# garden.net
KiCad netlist of a schematic drawn in EAGLE
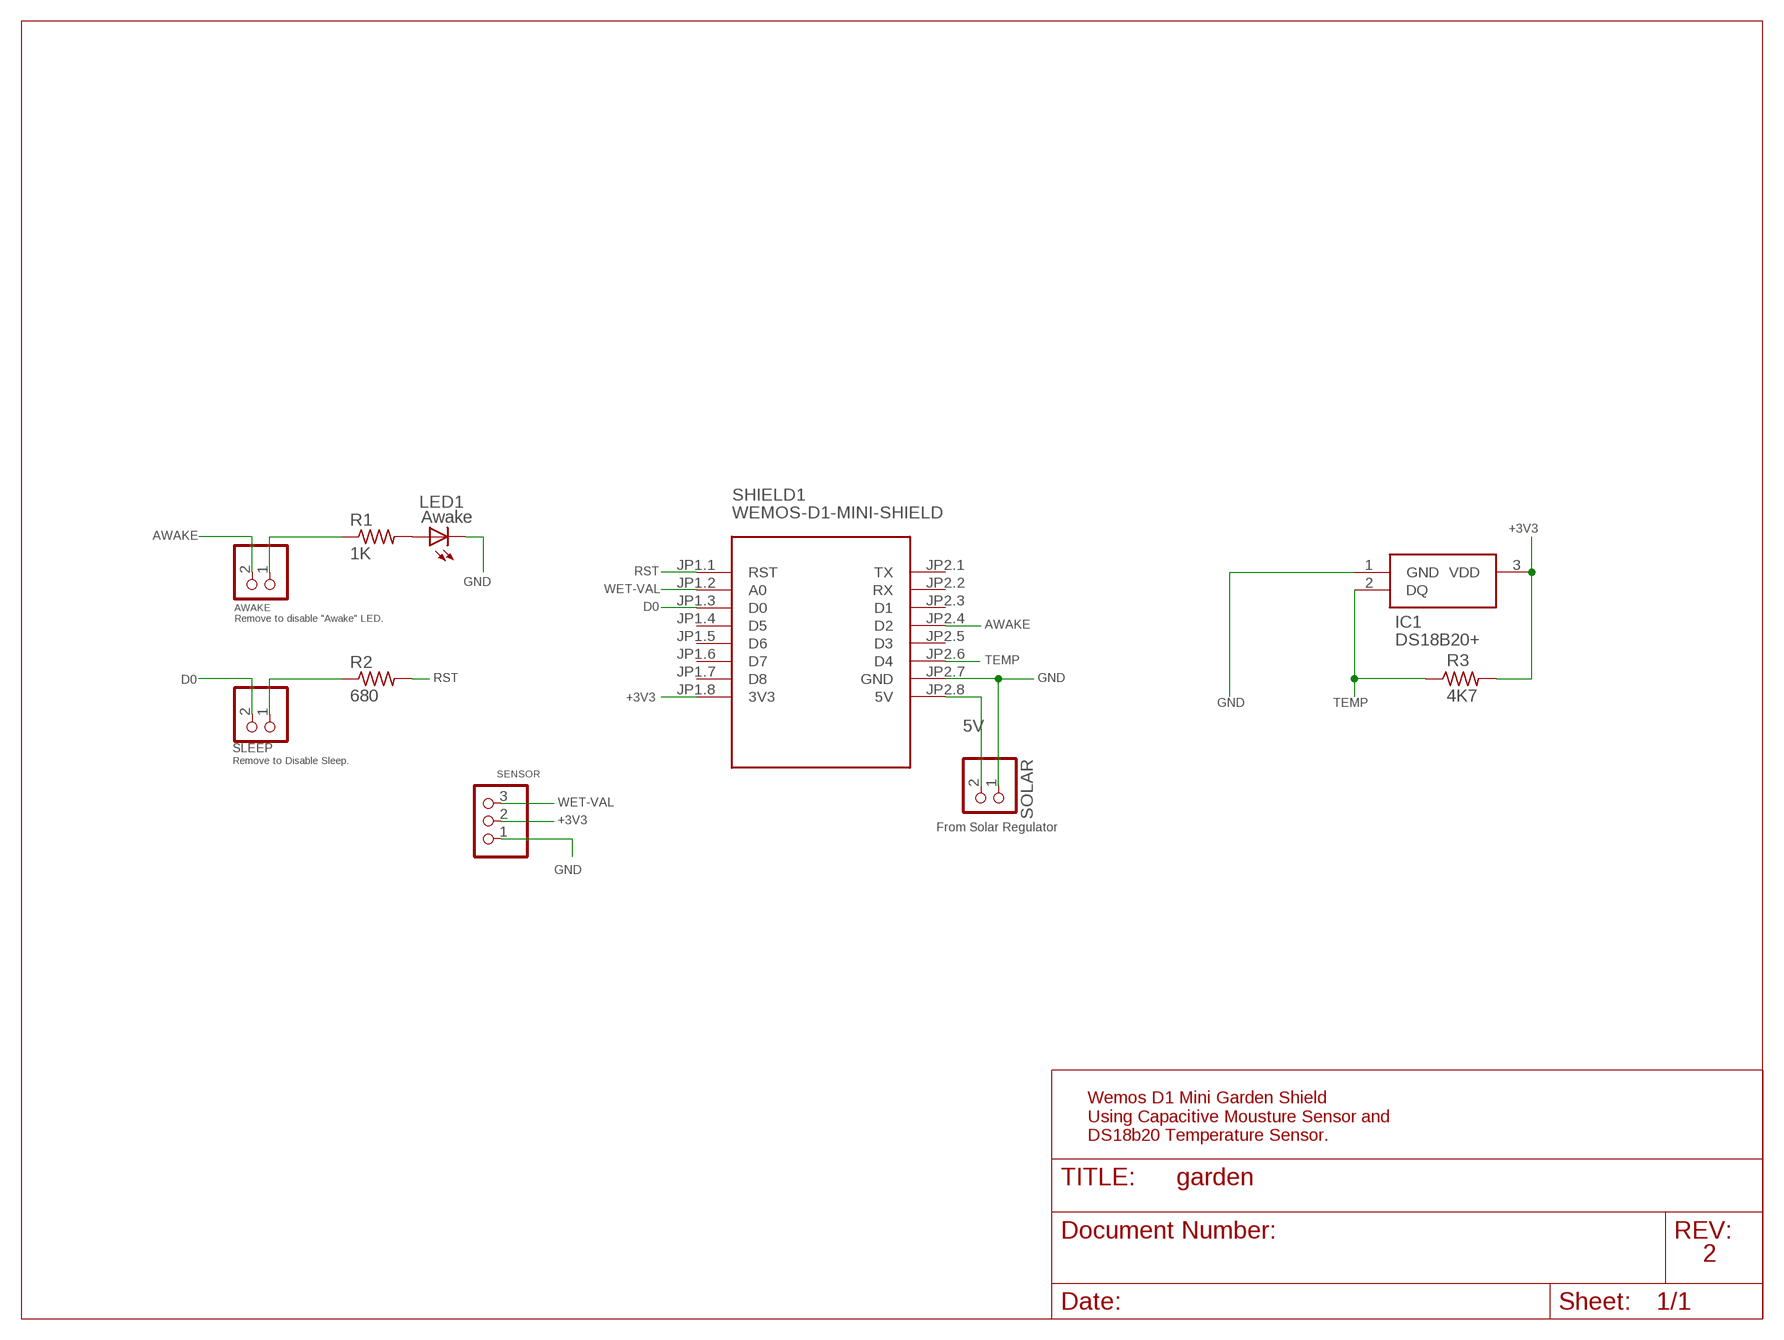
[diagram p0: schematic, sheet 1]

(export (version "E")
  (design (tool "Eeschema 10.0.6"))
  (components
    (comp (ref "AWAKE")
      (value "Remove to disable \"Awake\" LED.")
      (footprint "eagle-import:1X02")
      (libsource (lib "eagle-import") (part "PINHD-1X2"))
    )
    (comp (ref "IC1")
      (value "DS18B20+")
      (footprint "eagle-import:TO-92")
      (fields (field (name "MOUSER_PART_NUMBER") "700-DS18B20+"))
      (libsource (lib "eagle-import") (part "DS18B20+"))
    )
    (comp (ref "LED1")
      (value "Awake")
      (footprint "eagle-import:LED3MM")
      (libsource (lib "eagle-import") (part "LED3MM"))
    )
    (comp (ref "R1")
      (value "1K")
      (footprint "eagle-import:0207_9")
      (libsource (lib "eagle-import") (part "R-US_0207/9"))
    )
    (comp (ref "R2")
      (value "680")
      (footprint "eagle-import:0207_9")
      (libsource (lib "eagle-import") (part "R-US_0207/9"))
    )
    (comp (ref "R3")
      (value "4K7")
      (footprint "eagle-import:0207_9")
      (libsource (lib "eagle-import") (part "R-US_0207/9"))
    )
    (comp (ref "SENSOR")
      (value "Moisture Sensor")
      (footprint "eagle-import:1X03_90")
      (libsource (lib "eagle-import") (part "PINHD-1X3/90"))
    )
    (comp (ref "SHIELD1")
      (value "WEMOS-D1-MINI-SHIELD")
      (footprint "eagle-import:WEMOS-D1-MINI-SHIELD")
      (libsource (lib "eagle-import") (part "WEMOS-D1-MINI-SHIELD"))
    )
    (comp (ref "SLEEP")
      (value "Remove to Disable Sleep.")
      (footprint "eagle-import:1X02")
      (libsource (lib "eagle-import") (part "PINHD-1X2"))
    )
    (comp (ref "SOLAR")
      (value "From Solar Regulator")
      (footprint "eagle-import:1X02_90")
      (libsource (lib "eagle-import") (part "PINHD-1X2/90"))
    )
  )
  (nets
    (net (code "1") (name "/+3V3") (class "Default")
      (node (ref "IC1") (pin "3") (pinfunction "VDD_3") (pintype "power_in"))
      (node (ref "R3") (pin "2") (pinfunction "2_2") (pintype "passive"))
      (node (ref "SENSOR") (pin "2") (pinfunction "2_2") (pintype "passive"))
      (node (ref "SHIELD1") (pin "JP1.8") (pinfunction "3V3_JP1.8") (pintype "power_in"))
    )
    (net (code "2") (name "/5V") (class "Default")
      (node (ref "SHIELD1") (pin "JP2.8") (pinfunction "5V_JP2.8") (pintype "power_in"))
      (node (ref "SOLAR") (pin "2") (pinfunction "2_2") (pintype "passive"))
    )
    (net (code "3") (name "/AWAKE") (class "Default")
      (node (ref "AWAKE") (pin "2") (pinfunction "2_2") (pintype "passive"))
      (node (ref "SHIELD1") (pin "JP2.4") (pinfunction "D2_JP2.4") (pintype "bidirectional"))
    )
    (net (code "4") (name "/D0") (class "Default")
      (node (ref "SHIELD1") (pin "JP1.3") (pinfunction "D0_JP1.3") (pintype "bidirectional"))
      (node (ref "SLEEP") (pin "2") (pinfunction "2_2") (pintype "passive"))
    )
    (net (code "5") (name "/GND") (class "Default")
      (node (ref "IC1") (pin "1") (pinfunction "GND_1") (pintype "power_in"))
      (node (ref "LED1") (pin "K") (pinfunction "C_K") (pintype "passive"))
      (node (ref "SENSOR") (pin "1") (pinfunction "1_1") (pintype "passive"))
      (node (ref "SHIELD1") (pin "JP2.7") (pinfunction "GND_JP2.7") (pintype "power_in"))
      (node (ref "SOLAR") (pin "1") (pinfunction "1_1") (pintype "passive"))
    )
    (net (code "6") (name "/RST") (class "Default")
      (node (ref "R2") (pin "2") (pinfunction "2_2") (pintype "passive"))
      (node (ref "SHIELD1") (pin "JP1.1") (pinfunction "RST_JP1.1") (pintype "bidirectional"))
    )
    (net (code "7") (name "/TEMP") (class "Default")
      (node (ref "IC1") (pin "2") (pinfunction "DQ_2") (pintype "bidirectional"))
      (node (ref "R3") (pin "1") (pinfunction "1_1") (pintype "passive"))
      (node (ref "SHIELD1") (pin "JP2.6") (pinfunction "D4_JP2.6") (pintype "bidirectional"))
    )
    (net (code "8") (name "/WET-VAL") (class "Default")
      (node (ref "SENSOR") (pin "3") (pinfunction "3_3") (pintype "passive"))
      (node (ref "SHIELD1") (pin "JP1.2") (pinfunction "A0_JP1.2") (pintype "bidirectional"))
    )
    (net (code "9") (name "Net-(AWAKE-Pad1)") (class "Default")
      (node (ref "AWAKE") (pin "1") (pinfunction "1_1") (pintype "passive"))
      (node (ref "R1") (pin "1") (pinfunction "1_1") (pintype "passive"))
    )
    (net (code "10") (name "Net-(LED1-PadA)") (class "Default")
      (node (ref "LED1") (pin "A") (pinfunction "A_A") (pintype "passive"))
      (node (ref "R1") (pin "2") (pinfunction "2_2") (pintype "passive"))
    )
    (net (code "11") (name "Net-(R2-Pad1)") (class "Default")
      (node (ref "R2") (pin "1") (pinfunction "1_1") (pintype "passive"))
      (node (ref "SLEEP") (pin "1") (pinfunction "1_1") (pintype "passive"))
    )
    (net (code "12") (name "unconnected-(SHIELD1-D1-PadJP2.3)") (class "Default")
      (node (ref "SHIELD1") (pin "JP2.3") (pinfunction "D1_JP2.3") (pintype "bidirectional"))
    )
    (net (code "13") (name "unconnected-(SHIELD1-D3-PadJP2.5)") (class "Default")
      (node (ref "SHIELD1") (pin "JP2.5") (pinfunction "D3_JP2.5") (pintype "bidirectional"))
    )
    (net (code "14") (name "unconnected-(SHIELD1-D5-PadJP1.4)") (class "Default")
      (node (ref "SHIELD1") (pin "JP1.4") (pinfunction "D5_JP1.4") (pintype "bidirectional"))
    )
    (net (code "15") (name "unconnected-(SHIELD1-D6-PadJP1.5)") (class "Default")
      (node (ref "SHIELD1") (pin "JP1.5") (pinfunction "D6_JP1.5") (pintype "bidirectional"))
    )
    (net (code "16") (name "unconnected-(SHIELD1-D7-PadJP1.6)") (class "Default")
      (node (ref "SHIELD1") (pin "JP1.6") (pinfunction "D7_JP1.6") (pintype "bidirectional"))
    )
    (net (code "17") (name "unconnected-(SHIELD1-D8-PadJP1.7)") (class "Default")
      (node (ref "SHIELD1") (pin "JP1.7") (pinfunction "D8_JP1.7") (pintype "bidirectional"))
    )
    (net (code "18") (name "unconnected-(SHIELD1-RX-PadJP2.2)") (class "Default")
      (node (ref "SHIELD1") (pin "JP2.2") (pinfunction "RX_JP2.2") (pintype "bidirectional"))
    )
    (net (code "19") (name "unconnected-(SHIELD1-TX-PadJP2.1)") (class "Default")
      (node (ref "SHIELD1") (pin "JP2.1") (pinfunction "TX_JP2.1") (pintype "bidirectional"))
    )
  )
)
